# RGBReceiverRF.net
KiCad netlist of a schematic drawn in Altium Designer
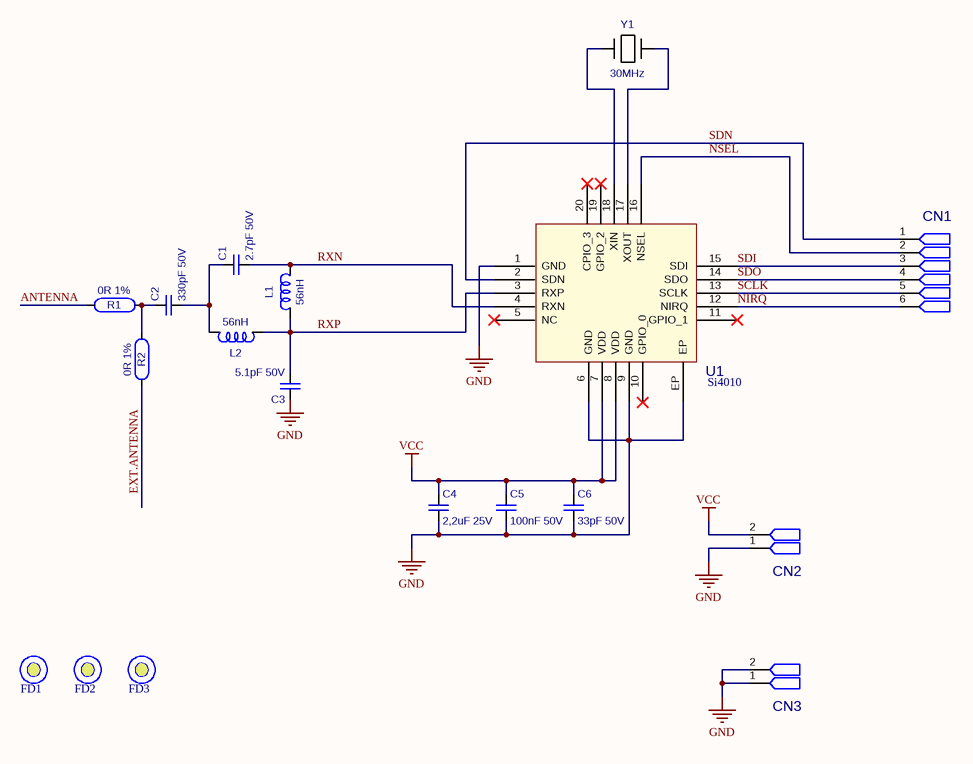
[diagram p0: RGBReceiverRF.SchDoc]

(export (version "E")
  (design (tool "Eeschema 10.0.6"))
  (components
    (comp (ref "C1")
      (value "2.7pF 50V")
      (footprint "C0805")
      (fields (field (name "PART NUMBER") "VJ0805A2R7CXAPW1BC"))
      (libsource (lib "GLOBUS_ALTIUM") (part "CC 2.7pF 50V 0805"))
    )
    (comp (ref "C2")
      (value "330pF 50V")
      (footprint "C0805")
      (fields (field (name "PART NUMBER") "08055A271JAT2A") (field (name "Comment") "270pF 50V"))
      (libsource (lib "GLOBUS_ALTIUM") (part "CC 270pF 50V 0805"))
    )
    (comp (ref "C3")
      (value "5.1pF 50V")
      (footprint "C0805")
      (fields (field (name "PART NUMBER") "08055A5R1CAT2A"))
      (libsource (lib "GLOBUS_ALTIUM") (part "CC 5.1pF 50V 0805"))
    )
    (comp (ref "C4")
      (value "2,2uF 25V")
      (footprint "C1206")
      (libsource (lib "GLOBUS_ALTIUM") (part "CC 2,2uF 25V 1206"))
    )
    (comp (ref "C5")
      (value "100nF 50V")
      (footprint "C0805")
      (libsource (lib "GLOBUS_ALTIUM") (part "CC 100nF 50V 0805"))
    )
    (comp (ref "C6")
      (value "33pF 50V")
      (footprint "C0805")
      (libsource (lib "GLOBUS_ALTIUM") (part "CC 33pF 50V 0805"))
    )
    (comp (ref "CN1")
      (value "CON BARRA 1x6 180 MACHO PTH")
      (footprint "BARRA6PM180")
      (description "Barra de pinos simples 1x6 180g. 2,54mm")
      (fields (field (name "PART NUMBER") "{Part Number}"))
      (libsource (lib "GLOBUS_ALTIUM") (part "CON BARRA 1x6 180 MACHO PTH"))
    )
    (comp (ref "CN2")
      (value "CON BARRA 1x2 180 MACHO PTH")
      (footprint "BARRA2PM180")
      (description "Barra de pinos simples 1x2 180g. 2,54mm")
      (fields (field (name "PART NUMBER") "{Part Number}"))
      (libsource (lib "GLOBUS_ALTIUM") (part "CON BARRA 1x2 180 MACHO PTH"))
    )
    (comp (ref "CN3")
      (value "CON BARRA 1x2 180 MACHO PTH")
      (footprint "BARRA2PM180")
      (description "Barra de pinos simples 1x2 180g. 2,54mm")
      (fields (field (name "PART NUMBER") "{Part Number}"))
      (libsource (lib "GLOBUS_ALTIUM") (part "CON BARRA 1x2 180 MACHO PTH"))
    )
    (comp (ref "FD1")
      (value "Fiducial")
      (footprint "Fiducial")
      (libsource (lib "GLOBUS_ALTIUM") (part "Fiducial"))
    )
    (comp (ref "FD2")
      (value "Fiducial")
      (footprint "Fiducial")
      (libsource (lib "GLOBUS_ALTIUM") (part "Fiducial"))
    )
    (comp (ref "FD3")
      (value "Fiducial")
      (footprint "Fiducial")
      (libsource (lib "GLOBUS_ALTIUM") (part "Fiducial"))
    )
    (comp (ref "L1")
      (value "56nH")
      (footprint "I0805")
      (description "IND 56nH 0805 SMD")
      (fields (field (name "PART NUMBER") "IMC0805ER56NJ01"))
      (libsource (lib "GLOBUS_ALTIUM") (part "IND 56nH 0805 SMD"))
    )
    (comp (ref "L2")
      (value "56nH")
      (footprint "I0805")
      (description "IND 56nH 0805 SMD")
      (fields (field (name "PART NUMBER") "IMC0805ER56NJ01"))
      (libsource (lib "GLOBUS_ALTIUM") (part "IND 56nH 0805 SMD"))
    )
    (comp (ref "R1")
      (value "0R 1%")
      (footprint "R0805")
      (description "RES 0R 1% 0805")
      (fields (field (name "PART NUMBER") "{Part Number}"))
      (libsource (lib "GLOBUS_ALTIUM") (part "RES 0R 1% 0805"))
    )
    (comp (ref "R2")
      (value "0R 1%")
      (footprint "R0805")
      (description "RES 0R 1% 0805")
      (fields (field (name "PART NUMBER") "{Part Number}"))
      (libsource (lib "GLOBUS_ALTIUM") (part "RES 0R 1% 0805"))
    )
    (comp (ref "U1")
      (value "Si4010")
      (footprint "QFN20 3X3")
      (description "CI Si4355 QFN20")
      (fields (field (name "PART NUMBER") "Si4355-B1A-FM"))
      (libsource (lib "GLOBUS_ALTIUM") (part "CI Si4355 QFN20"))
    )
    (comp (ref "Y1")
      (value "30MHz")
      (footprint "ABLS SMD")
      (description "XTAL 30MHZ ABLS-SMC")
      (fields (field (name "PART NUMBER") "ABLS-30.000MHZ-B4-F-T"))
      (libsource (lib "GLOBUS_ALTIUM") (part "XTAL 30MHZ ABLS-SMC"))
    )
  )
  (nets
    (net (code "1") (name "/ANTENNA") (class "Default")
      (node (ref "R1") (pin "1") (pinfunction "1_1") (pintype "passive"))
    )
    (net (code "2") (name "/EXT.ANTENNA") (class "Default")
      (node (ref "R2") (pin "1") (pinfunction "1_1") (pintype "passive"))
    )
    (net (code "3") (name "/NIRQ") (class "Default")
      (node (ref "CN1") (pin "6") (pinfunction "6_6") (pintype "passive"))
      (node (ref "U1") (pin "12") (pinfunction "NIRQ_12") (pintype "passive"))
    )
    (net (code "4") (name "/NSEL") (class "Default")
      (node (ref "CN1") (pin "2") (pinfunction "2_2") (pintype "passive"))
      (node (ref "U1") (pin "16") (pinfunction "NSEL_16") (pintype "passive"))
    )
    (net (code "5") (name "/RXN") (class "Default")
      (node (ref "C1") (pin "2") (pinfunction "2_2") (pintype "passive"))
      (node (ref "L1") (pin "2") (pinfunction "2_2") (pintype "passive"))
      (node (ref "U1") (pin "4") (pinfunction "RXN_4") (pintype "passive"))
    )
    (net (code "6") (name "/RXP") (class "Default")
      (node (ref "C3") (pin "2") (pinfunction "2_2") (pintype "passive"))
      (node (ref "L1") (pin "1") (pinfunction "1_1") (pintype "passive"))
      (node (ref "L2") (pin "1") (pinfunction "1_1") (pintype "passive"))
      (node (ref "U1") (pin "3") (pinfunction "RXP_3") (pintype "passive"))
    )
    (net (code "7") (name "/SCLK") (class "Default")
      (node (ref "CN1") (pin "5") (pinfunction "5_5") (pintype "passive"))
      (node (ref "U1") (pin "13") (pinfunction "SCLK_13") (pintype "passive"))
    )
    (net (code "8") (name "/SDI") (class "Default")
      (node (ref "CN1") (pin "3") (pinfunction "3_3") (pintype "passive"))
      (node (ref "U1") (pin "15") (pinfunction "SDI_15") (pintype "passive"))
    )
    (net (code "9") (name "/SDN") (class "Default")
      (node (ref "CN1") (pin "1") (pinfunction "1_1") (pintype "passive"))
      (node (ref "U1") (pin "2") (pinfunction "SDN_2") (pintype "passive"))
    )
    (net (code "10") (name "/SDO") (class "Default")
      (node (ref "CN1") (pin "4") (pinfunction "4_4") (pintype "passive"))
      (node (ref "U1") (pin "14") (pinfunction "SDO_14") (pintype "passive"))
    )
    (net (code "11") (name "GND") (class "Default")
      (node (ref "C3") (pin "1") (pinfunction "1_1") (pintype "passive"))
      (node (ref "C4") (pin "2") (pinfunction "2_2") (pintype "passive"))
      (node (ref "C5") (pin "2") (pinfunction "2_2") (pintype "passive"))
      (node (ref "C6") (pin "2") (pinfunction "2_2") (pintype "passive"))
      (node (ref "CN2") (pin "1") (pinfunction "1_1") (pintype "passive"))
      (node (ref "CN3") (pin "1") (pinfunction "1_1") (pintype "passive"))
      (node (ref "CN3") (pin "2") (pinfunction "2_2") (pintype "passive"))
      (node (ref "U1") (pin "1") (pinfunction "GND_1") (pintype "passive"))
      (node (ref "U1") (pin "6") (pinfunction "GND_6") (pintype "passive"))
      (node (ref "U1") (pin "9") (pinfunction "GND_9") (pintype "passive"))
      (node (ref "U1") (pin "EP") (pinfunction "EP_EP") (pintype "passive"))
    )
    (net (code "12") (name "Net-(C1-Pad1)") (class "Default")
      (node (ref "C1") (pin "1") (pinfunction "1_1") (pintype "passive"))
      (node (ref "C2") (pin "2") (pinfunction "2_2") (pintype "passive"))
      (node (ref "L2") (pin "2") (pinfunction "2_2") (pintype "passive"))
    )
    (net (code "13") (name "Net-(C2-Pad1)") (class "Default")
      (node (ref "C2") (pin "1") (pinfunction "1_1") (pintype "passive"))
      (node (ref "R1") (pin "2") (pinfunction "2_2") (pintype "passive"))
      (node (ref "R2") (pin "2") (pinfunction "2_2") (pintype "passive"))
    )
    (net (code "14") (name "Net-(U1-XIN)") (class "Default")
      (node (ref "U1") (pin "18") (pinfunction "XIN_18") (pintype "passive"))
      (node (ref "Y1") (pin "1") (pinfunction "1_1") (pintype "passive"))
    )
    (net (code "15") (name "Net-(U1-XOUT)") (class "Default")
      (node (ref "U1") (pin "17") (pinfunction "XOUT_17") (pintype "passive"))
      (node (ref "Y1") (pin "2") (pinfunction "2_2") (pintype "passive"))
    )
    (net (code "16") (name "VCC") (class "Default")
      (node (ref "C4") (pin "1") (pinfunction "1_1") (pintype "passive"))
      (node (ref "C5") (pin "1") (pinfunction "1_1") (pintype "passive"))
      (node (ref "C6") (pin "1") (pinfunction "1_1") (pintype "passive"))
      (node (ref "CN2") (pin "2") (pinfunction "2_2") (pintype "passive"))
      (node (ref "U1") (pin "7") (pinfunction "VDD_7") (pintype "passive"))
      (node (ref "U1") (pin "8") (pinfunction "VDD_8") (pintype "passive"))
    )
    (net (code "17") (name "unconnected-(U1-CPIO_3-Pad20)") (class "Default")
      (node (ref "U1") (pin "20") (pinfunction "CPIO_3_20") (pintype "passive+no_connect"))
    )
    (net (code "18") (name "unconnected-(U1-GPIO_0-Pad10)") (class "Default")
      (node (ref "U1") (pin "10") (pinfunction "GPIO_0_10") (pintype "passive+no_connect"))
    )
    (net (code "19") (name "unconnected-(U1-GPIO_1-Pad11)") (class "Default")
      (node (ref "U1") (pin "11") (pinfunction "GPIO_1_11") (pintype "passive+no_connect"))
    )
    (net (code "20") (name "unconnected-(U1-GPIO_2-Pad19)") (class "Default")
      (node (ref "U1") (pin "19") (pinfunction "GPIO_2_19") (pintype "passive+no_connect"))
    )
    (net (code "21") (name "unconnected-(U1-NC-Pad5)") (class "Default")
      (node (ref "U1") (pin "5") (pinfunction "NC_5") (pintype "passive+no_connect"))
    )
  )
)
